# DRIVERS_CONNECTORS.net
KiCad netlist of a schematic drawn in Altium Designer
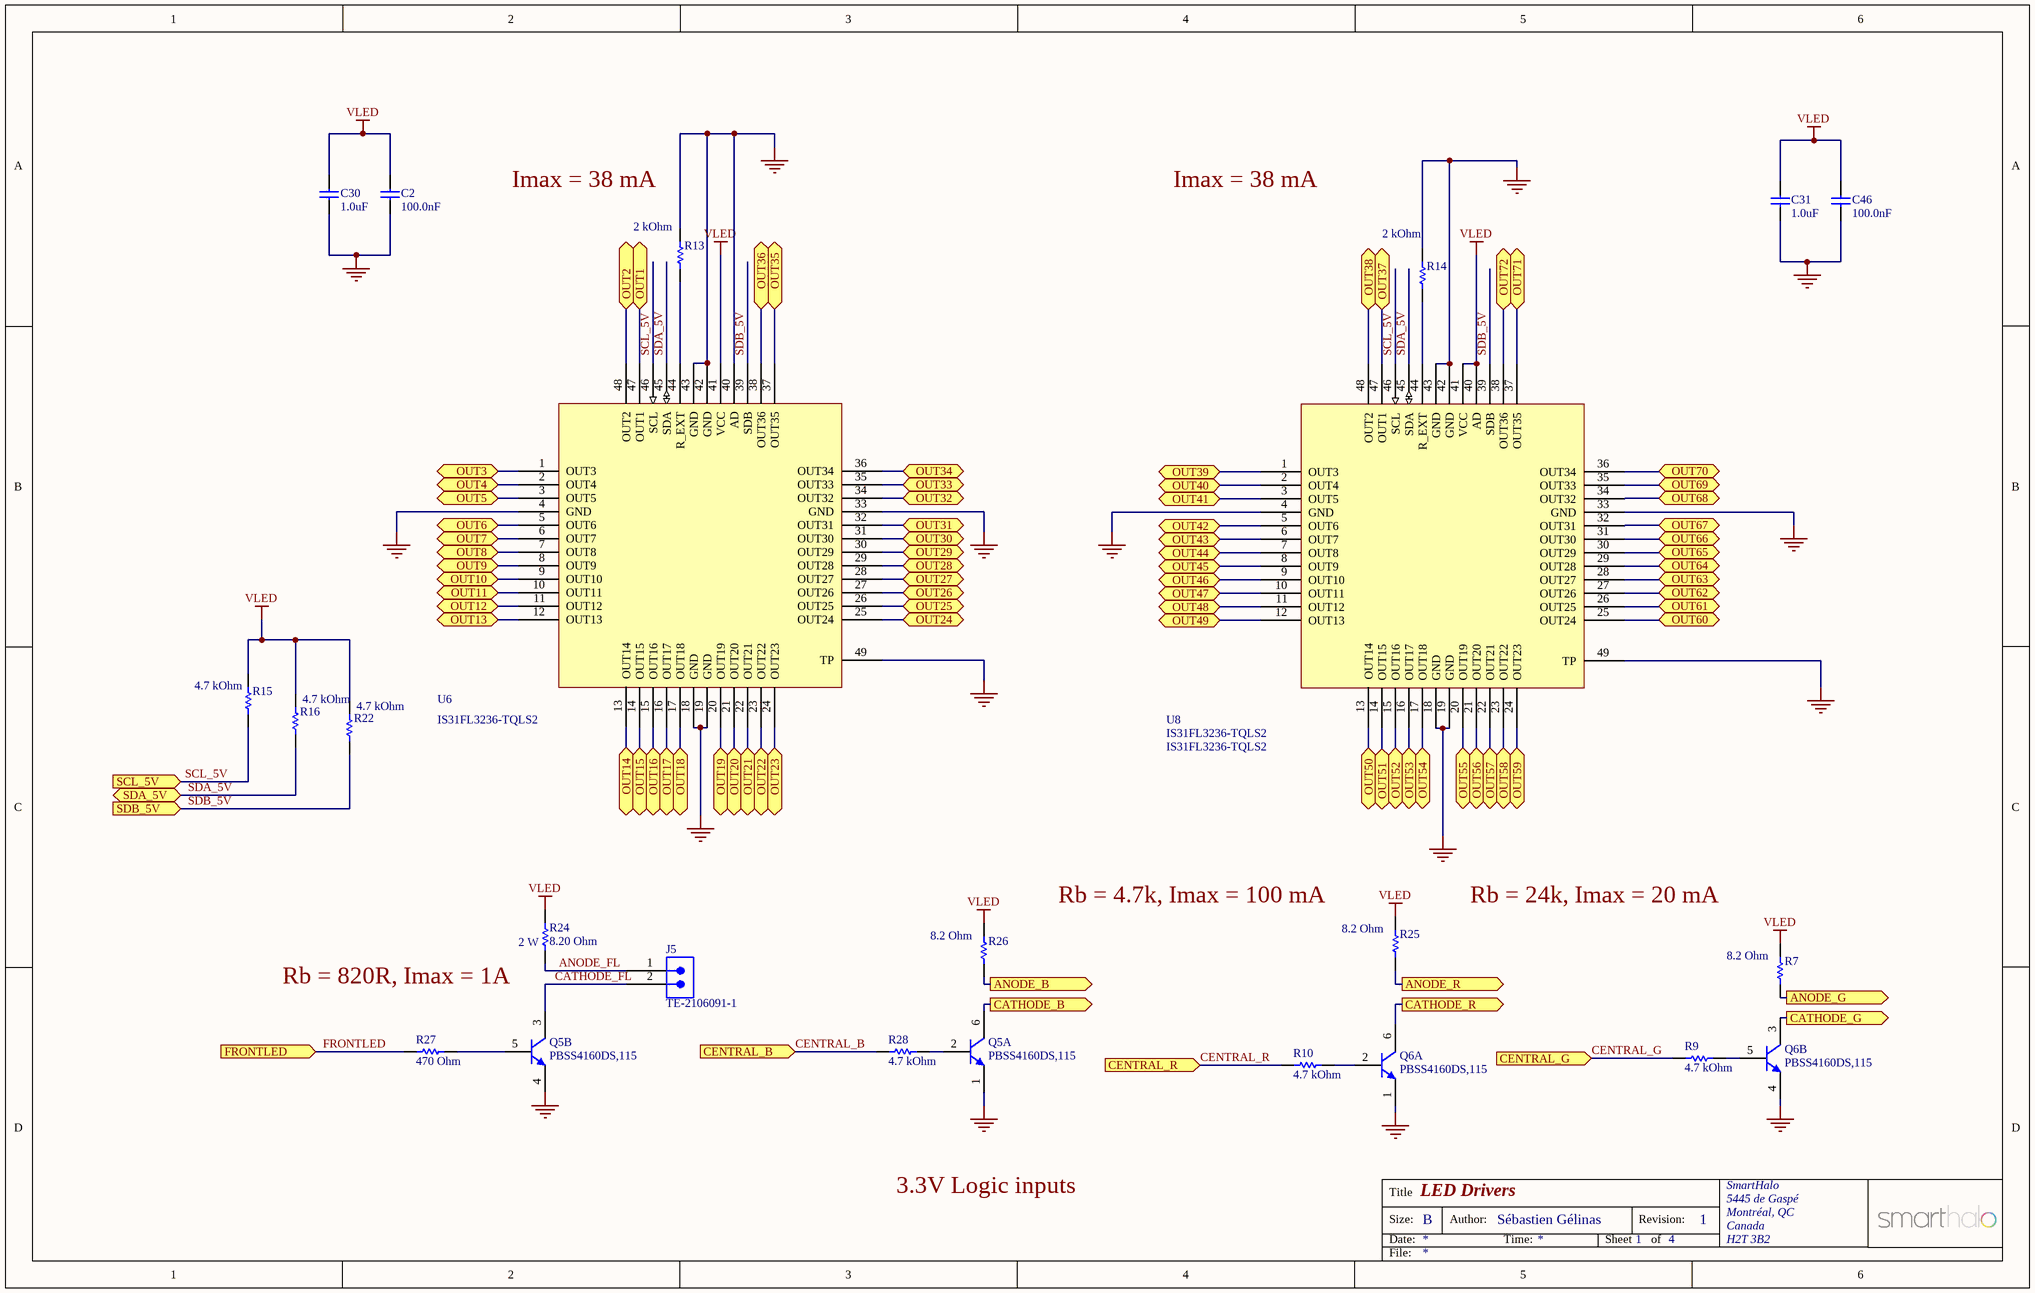
[diagram p0: DRIVERS_CONNECTORS.SchDoc]

(export (version "E")
  (design (tool "Eeschema 10.0.6"))
  (components
    (comp (ref "C2")
      (value "100.0nF")
      (footprint "CAPC0603(1608)100_N")
      (description "Chip Cap 0603 X7R 10%")
      (fields (field (name "PART NUMBER") "C0402-1n0") (field (name "PUBLISHER") "Nordic Semiconductor"))
      (libsource (lib "SmartHalo") (part "CAP0603"))
    )
    (comp (ref "C30")
      (value "1.0uF")
      (footprint "CAPC0603(1608)100_N")
      (description "Chip Cap 0603 X7R 10%")
      (fields (field (name "PART NUMBER") "C0402-1n0") (field (name "PUBLISHER") "Nordic Semiconductor"))
      (libsource (lib "SmartHalo") (part "CAP0603"))
    )
    (comp (ref "C31")
      (value "1.0uF")
      (footprint "CAPC0603(1608)100_N")
      (description "Chip Cap 0603 X7R 10%")
      (fields (field (name "PART NUMBER") "C0402-1n0") (field (name "PUBLISHER") "Nordic Semiconductor"))
      (libsource (lib "SmartHalo") (part "CAP0603"))
    )
    (comp (ref "C46")
      (value "100.0nF")
      (footprint "CAPC0603(1608)100_N")
      (description "Chip Cap 0603 X7R 10%")
      (fields (field (name "PART NUMBER") "C0402-1n0") (field (name "PUBLISHER") "Nordic Semiconductor"))
      (libsource (lib "SmartHalo") (part "CAP0603"))
    )
    (comp (ref "J5")
      (value "TE-2106091-1")
      (footprint "TE-2106091-1")
      (description "2 pos Inverted Thru Board SMT Header")
      (fields (field (name "MANUFACTURER") "TE") (field (name "MANUFACTURER PART NUMBER") "2106091"))
      (libsource (lib "SmartHalo") (part "TE-2106091-1"))
    )
    (comp (ref "Q5")
      (value "PBSS4160DS,115")
      (footprint "SmartHalo:NXP-SC74_M")
      (description "TRANS 2NPN 60V 1A 6TSOP")
      (fields (field (name "PARTNUMBER") "PBSS4160DS") (field (name "MANUFACTURER") "NXP Semiconductors"))
      (libsource (lib "SmartHalo_Symbols") (part "PBSS4160DS,115"))
    )
    (comp (ref "Q6")
      (value "PBSS4160DS,115")
      (footprint "SmartHalo:NXP-SC74_M")
      (description "TRANS 2NPN 60V 1A 6TSOP")
      (fields (field (name "PARTNUMBER") "PBSS4160DS") (field (name "MANUFACTURER") "NXP Semiconductors"))
      (libsource (lib "SmartHalo_Symbols") (part "PBSS4160DS,115"))
    )
    (comp (ref "R7")
      (value "8.2 Ohm")
      (footprint "RESC0603(1608)_N")
      (description "8R2 0.1W 5% 0603 (1608 Metric)  SMD")
      (fields (field (name "TOLERANCE") "5 %") (field (name "POWER") "0.1 W"))
      (libsource (lib "Altium Content Vault") (part "CMP-1012-00090-1"))
    )
    (comp (ref "R9")
      (value "4.7 kOhm")
      (footprint "RESC0603(1608)_N")
      (description "4K7 0.1W 5% 0603 (1608 Metric)  SMD")
      (fields (field (name "TOLERANCE") "5 %") (field (name "POWER") "0.1 W"))
      (libsource (lib "Altium Content Vault") (part "CMP-1012-00090-1"))
    )
    (comp (ref "R10")
      (value "4.7 kOhm")
      (footprint "RESC0603(1608)_N")
      (description "4K7 0.1W 5% 0603 (1608 Metric)  SMD")
      (fields (field (name "TOLERANCE") "5 %") (field (name "POWER") "0.1 W"))
      (libsource (lib "Altium Content Vault") (part "CMP-1012-00090-1"))
    )
    (comp (ref "R13")
      (value "2 kOhm")
      (footprint "RESC0603(1608)_N")
      (description "2k 0.1W 5% 0603 (1608 Metric)  SMD")
      (fields (field (name "TOLERANCE") "5 %") (field (name "POWER") "0.1 W"))
      (libsource (lib "Altium Content Vault") (part "CMP-1012-00090-1"))
    )
    (comp (ref "R14")
      (value "2 kOhm")
      (footprint "RESC0603(1608)_N")
      (description "2k 0.1W 5% 0603 (1608 Metric)  SMD")
      (fields (field (name "TOLERANCE") "5 %") (field (name "POWER") "0.1 W"))
      (libsource (lib "Altium Content Vault") (part "CMP-1012-00090-1"))
    )
    (comp (ref "R15")
      (value "4.7 kOhm")
      (footprint "RESC0603(1608)_N")
      (description "4K7 0.1W 5% 0603 (1608 Metric)  SMD")
      (fields (field (name "TOLERANCE") "5 %") (field (name "POWER") "0.1 W"))
      (libsource (lib "Altium Content Vault") (part "CMP-1012-00090-1"))
    )
    (comp (ref "R16")
      (value "4.7 kOhm")
      (footprint "RESC0603(1608)_N")
      (description "4K7 0.1W 5% 0603 (1608 Metric)  SMD")
      (fields (field (name "TOLERANCE") "5 %") (field (name "POWER") "0.1 W"))
      (libsource (lib "Altium Content Vault") (part "CMP-1012-00090-1"))
    )
    (comp (ref "R22")
      (value "4.7 kOhm")
      (footprint "RESC0603(1608)_N")
      (description "4K7 0.1W 5% 0603 (1608 Metric)  SMD")
      (fields (field (name "TOLERANCE") "5 %") (field (name "POWER") "0.1 W"))
      (libsource (lib "Altium Content Vault") (part "CMP-1012-00090-1"))
    )
    (comp (ref "R24")
      (value "8.20 Ohm")
      (footprint "RESC2512(6432)_L")
      (description "8R2 2W 5% 2512 (6432 Metric)  SMD")
      (fields (field (name "TOLERANCE") "5 %") (field (name "POWER") "2 W"))
      (libsource (lib "Altium Content Vault") (part "CMP-1018-00024-1"))
    )
    (comp (ref "R25")
      (value "8.2 Ohm")
      (footprint "RESC0603(1608)_N")
      (description "8R2 0.1W 5% 0603 (1608 Metric)  SMD")
      (fields (field (name "TOLERANCE") "5 %") (field (name "POWER") "0.1 W"))
      (libsource (lib "Altium Content Vault") (part "CMP-1012-00090-1"))
    )
    (comp (ref "R26")
      (value "8.2 Ohm")
      (footprint "RESC0603(1608)_N")
      (description "8R2 0.1W 5% 0603 (1608 Metric)  SMD")
      (fields (field (name "TOLERANCE") "5 %") (field (name "POWER") "0.1 W"))
      (libsource (lib "Altium Content Vault") (part "CMP-1012-00090-1"))
    )
    (comp (ref "R27")
      (value "470 Ohm")
      (footprint "RESC0603(1608)_N")
      (description "470R 1/16W 5% 0603 (1608 Metric)  SMD")
      (fields (field (name "TOLERANCE") "5 %") (field (name "POWER") "1/16 W"))
      (libsource (lib "Altium Content Vault") (part "CMP-1012-00090-1"))
    )
    (comp (ref "R28")
      (value "4.7 kOhm")
      (footprint "RESC0603(1608)_N")
      (description "4K7 0.1W 5% 0603 (1608 Metric)  SMD")
      (fields (field (name "TOLERANCE") "5 %") (field (name "POWER") "0.1 W"))
      (libsource (lib "Altium Content Vault") (part "CMP-1012-00090-1"))
    )
    (comp (ref "U6")
      (value "IS31FL3236-TQLS2")
      (footprint "TQFP48")
      (description "IC 36 CHANNELS LED DRIVER")
      (fields (field (name "MANUFACTURER") "ISSI"))
      (libsource (lib "SmartHalo") (part "IS31FL3236-TQLS2"))
    )
    (comp (ref "U8")
      (value "IS31FL3236-TQLS2")
      (footprint "TQFP48")
      (description "IC 36 CHANNELS LED DRIVER")
      (fields
        (field (name "MANUFACTURER") "ISSI")
        (field (name "MANUFACTURER PART NUMBER") "IS31FL3236-TQLS2")
      )
      (libsource (lib "SmartHalo") (part "IS31FL3236-TQLS2"))
    )
  )
  (nets
    (net (code "1") (name "/ANODE_B") (class "Default")
      (node (ref "R26") (pin "1") (pinfunction "1_1") (pintype "passive"))
    )
    (net (code "2") (name "/ANODE_FL") (class "Default")
      (node (ref "J5") (pin "1") (pinfunction "1_1") (pintype "passive"))
      (node (ref "R24") (pin "1") (pinfunction "1_1") (pintype "passive"))
    )
    (net (code "3") (name "/ANODE_G") (class "Default")
      (node (ref "R7") (pin "1") (pinfunction "1_1") (pintype "passive"))
    )
    (net (code "4") (name "/ANODE_R") (class "Default")
      (node (ref "R25") (pin "1") (pinfunction "1_1") (pintype "passive"))
    )
    (net (code "5") (name "/CATHODE_B") (class "Default")
      (node (ref "Q5") (pin "6") (pinfunction "C1_6") (pintype "passive"))
    )
    (net (code "6") (name "/CATHODE_FL") (class "Default")
      (node (ref "J5") (pin "2") (pinfunction "2_2") (pintype "passive"))
      (node (ref "Q5") (pin "3") (pinfunction "C2_3") (pintype "passive"))
    )
    (net (code "7") (name "/CATHODE_G") (class "Default")
      (node (ref "Q6") (pin "3") (pinfunction "C2_3") (pintype "passive"))
    )
    (net (code "8") (name "/CATHODE_R") (class "Default")
      (node (ref "Q6") (pin "6") (pinfunction "C1_6") (pintype "passive"))
    )
    (net (code "9") (name "/CENTRAL_B") (class "Default")
      (node (ref "R28") (pin "2") (pinfunction "2_2") (pintype "passive"))
    )
    (net (code "10") (name "/CENTRAL_G") (class "Default")
      (node (ref "R9") (pin "2") (pinfunction "2_2") (pintype "passive"))
    )
    (net (code "11") (name "/CENTRAL_R") (class "Default")
      (node (ref "R10") (pin "2") (pinfunction "2_2") (pintype "passive"))
    )
    (net (code "12") (name "/FRONTLED") (class "Default")
      (node (ref "R27") (pin "2") (pinfunction "2_2") (pintype "passive"))
    )
    (net (code "13") (name "/OUT1") (class "Default")
      (node (ref "U6") (pin "47") (pinfunction "OUT1_47") (pintype "passive"))
    )
    (net (code "14") (name "/OUT2") (class "Default")
      (node (ref "U6") (pin "48") (pinfunction "OUT2_48") (pintype "passive"))
    )
    (net (code "15") (name "/OUT3") (class "Default")
      (node (ref "U6") (pin "1") (pinfunction "OUT3_1") (pintype "passive"))
    )
    (net (code "16") (name "/OUT4") (class "Default")
      (node (ref "U6") (pin "2") (pinfunction "OUT4_2") (pintype "passive"))
    )
    (net (code "17") (name "/OUT5") (class "Default")
      (node (ref "U6") (pin "3") (pinfunction "OUT5_3") (pintype "passive"))
    )
    (net (code "18") (name "/OUT6") (class "Default")
      (node (ref "U6") (pin "5") (pinfunction "OUT6_5") (pintype "passive"))
    )
    (net (code "19") (name "/OUT7") (class "Default")
      (node (ref "U6") (pin "6") (pinfunction "OUT7_6") (pintype "passive"))
    )
    (net (code "20") (name "/OUT8") (class "Default")
      (node (ref "U6") (pin "7") (pinfunction "OUT8_7") (pintype "passive"))
    )
    (net (code "21") (name "/OUT9") (class "Default")
      (node (ref "U6") (pin "8") (pinfunction "OUT9_8") (pintype "passive"))
    )
    (net (code "22") (name "/OUT10") (class "Default")
      (node (ref "U6") (pin "9") (pinfunction "OUT10_9") (pintype "passive"))
    )
    (net (code "23") (name "/OUT11") (class "Default")
      (node (ref "U6") (pin "10") (pinfunction "OUT11_10") (pintype "passive"))
    )
    (net (code "24") (name "/OUT12") (class "Default")
      (node (ref "U6") (pin "11") (pinfunction "OUT12_11") (pintype "passive"))
    )
    (net (code "25") (name "/OUT13") (class "Default")
      (node (ref "U6") (pin "12") (pinfunction "OUT13_12") (pintype "passive"))
    )
    (net (code "26") (name "/OUT14") (class "Default")
      (node (ref "U6") (pin "13") (pinfunction "OUT14_13") (pintype "passive"))
    )
    (net (code "27") (name "/OUT15") (class "Default")
      (node (ref "U6") (pin "14") (pinfunction "OUT15_14") (pintype "passive"))
    )
    (net (code "28") (name "/OUT16") (class "Default")
      (node (ref "U6") (pin "15") (pinfunction "OUT16_15") (pintype "passive"))
    )
    (net (code "29") (name "/OUT17") (class "Default")
      (node (ref "U6") (pin "16") (pinfunction "OUT17_16") (pintype "passive"))
    )
    (net (code "30") (name "/OUT18") (class "Default")
      (node (ref "U6") (pin "17") (pinfunction "OUT18_17") (pintype "passive"))
    )
    (net (code "31") (name "/OUT19") (class "Default")
      (node (ref "U6") (pin "20") (pinfunction "OUT19_20") (pintype "passive"))
    )
    (net (code "32") (name "/OUT20") (class "Default")
      (node (ref "U6") (pin "21") (pinfunction "OUT20_21") (pintype "passive"))
    )
    (net (code "33") (name "/OUT21") (class "Default")
      (node (ref "U6") (pin "22") (pinfunction "OUT21_22") (pintype "passive"))
    )
    (net (code "34") (name "/OUT22") (class "Default")
      (node (ref "U6") (pin "23") (pinfunction "OUT22_23") (pintype "passive"))
    )
    (net (code "35") (name "/OUT23") (class "Default")
      (node (ref "U6") (pin "24") (pinfunction "OUT23_24") (pintype "passive"))
    )
    (net (code "36") (name "/OUT24") (class "Default")
      (node (ref "U6") (pin "25") (pinfunction "OUT24_25") (pintype "passive"))
    )
    (net (code "37") (name "/OUT25") (class "Default")
      (node (ref "U6") (pin "26") (pinfunction "OUT25_26") (pintype "passive"))
    )
    (net (code "38") (name "/OUT26") (class "Default")
      (node (ref "U6") (pin "27") (pinfunction "OUT26_27") (pintype "passive"))
    )
    (net (code "39") (name "/OUT27") (class "Default")
      (node (ref "U6") (pin "28") (pinfunction "OUT27_28") (pintype "passive"))
    )
    (net (code "40") (name "/OUT28") (class "Default")
      (node (ref "U6") (pin "29") (pinfunction "OUT28_29") (pintype "passive"))
    )
    (net (code "41") (name "/OUT29") (class "Default")
      (node (ref "U6") (pin "30") (pinfunction "OUT29_30") (pintype "passive"))
    )
    (net (code "42") (name "/OUT30") (class "Default")
      (node (ref "U6") (pin "31") (pinfunction "OUT30_31") (pintype "passive"))
    )
    (net (code "43") (name "/OUT31") (class "Default")
      (node (ref "U6") (pin "32") (pinfunction "OUT31_32") (pintype "passive"))
    )
    (net (code "44") (name "/OUT32") (class "Default")
      (node (ref "U6") (pin "34") (pinfunction "OUT32_34") (pintype "passive"))
    )
    (net (code "45") (name "/OUT33") (class "Default")
      (node (ref "U6") (pin "35") (pinfunction "OUT33_35") (pintype "passive"))
    )
    (net (code "46") (name "/OUT34") (class "Default")
      (node (ref "U6") (pin "36") (pinfunction "OUT34_36") (pintype "passive"))
    )
    (net (code "47") (name "/OUT35") (class "Default")
      (node (ref "U6") (pin "37") (pinfunction "OUT35_37") (pintype "passive"))
    )
    (net (code "48") (name "/OUT36") (class "Default")
      (node (ref "U6") (pin "38") (pinfunction "OUT36_38") (pintype "passive"))
    )
    (net (code "49") (name "/OUT37") (class "Default")
      (node (ref "U8") (pin "47") (pinfunction "OUT1_47") (pintype "passive"))
    )
    (net (code "50") (name "/OUT38") (class "Default")
      (node (ref "U8") (pin "48") (pinfunction "OUT2_48") (pintype "passive"))
    )
    (net (code "51") (name "/OUT39") (class "Default")
      (node (ref "U8") (pin "1") (pinfunction "OUT3_1") (pintype "passive"))
    )
    (net (code "52") (name "/OUT40") (class "Default")
      (node (ref "U8") (pin "2") (pinfunction "OUT4_2") (pintype "passive"))
    )
    (net (code "53") (name "/OUT41") (class "Default")
      (node (ref "U8") (pin "3") (pinfunction "OUT5_3") (pintype "passive"))
    )
    (net (code "54") (name "/OUT42") (class "Default")
      (node (ref "U8") (pin "5") (pinfunction "OUT6_5") (pintype "passive"))
    )
    (net (code "55") (name "/OUT43") (class "Default")
      (node (ref "U8") (pin "6") (pinfunction "OUT7_6") (pintype "passive"))
    )
    (net (code "56") (name "/OUT44") (class "Default")
      (node (ref "U8") (pin "7") (pinfunction "OUT8_7") (pintype "passive"))
    )
    (net (code "57") (name "/OUT45") (class "Default")
      (node (ref "U8") (pin "8") (pinfunction "OUT9_8") (pintype "passive"))
    )
    (net (code "58") (name "/OUT46") (class "Default")
      (node (ref "U8") (pin "9") (pinfunction "OUT10_9") (pintype "passive"))
    )
    (net (code "59") (name "/OUT47") (class "Default")
      (node (ref "U8") (pin "10") (pinfunction "OUT11_10") (pintype "passive"))
    )
    (net (code "60") (name "/OUT48") (class "Default")
      (node (ref "U8") (pin "11") (pinfunction "OUT12_11") (pintype "passive"))
    )
    (net (code "61") (name "/OUT49") (class "Default")
      (node (ref "U8") (pin "12") (pinfunction "OUT13_12") (pintype "passive"))
    )
    (net (code "62") (name "/OUT50") (class "Default")
      (node (ref "U8") (pin "13") (pinfunction "OUT14_13") (pintype "passive"))
    )
    (net (code "63") (name "/OUT51") (class "Default")
      (node (ref "U8") (pin "14") (pinfunction "OUT15_14") (pintype "passive"))
    )
    (net (code "64") (name "/OUT52") (class "Default")
      (node (ref "U8") (pin "15") (pinfunction "OUT16_15") (pintype "passive"))
    )
    (net (code "65") (name "/OUT53") (class "Default")
      (node (ref "U8") (pin "16") (pinfunction "OUT17_16") (pintype "passive"))
    )
    (net (code "66") (name "/OUT54") (class "Default")
      (node (ref "U8") (pin "17") (pinfunction "OUT18_17") (pintype "passive"))
    )
    (net (code "67") (name "/OUT55") (class "Default")
      (node (ref "U8") (pin "20") (pinfunction "OUT19_20") (pintype "passive"))
    )
    (net (code "68") (name "/OUT56") (class "Default")
      (node (ref "U8") (pin "21") (pinfunction "OUT20_21") (pintype "passive"))
    )
    (net (code "69") (name "/OUT57") (class "Default")
      (node (ref "U8") (pin "22") (pinfunction "OUT21_22") (pintype "passive"))
    )
    (net (code "70") (name "/OUT58") (class "Default")
      (node (ref "U8") (pin "23") (pinfunction "OUT22_23") (pintype "passive"))
    )
    (net (code "71") (name "/OUT59") (class "Default")
      (node (ref "U8") (pin "24") (pinfunction "OUT23_24") (pintype "passive"))
    )
    (net (code "72") (name "/OUT60") (class "Default")
      (node (ref "U8") (pin "25") (pinfunction "OUT24_25") (pintype "passive"))
    )
    (net (code "73") (name "/OUT61") (class "Default")
      (node (ref "U8") (pin "26") (pinfunction "OUT25_26") (pintype "passive"))
    )
    (net (code "74") (name "/OUT62") (class "Default")
      (node (ref "U8") (pin "27") (pinfunction "OUT26_27") (pintype "passive"))
    )
    (net (code "75") (name "/OUT63") (class "Default")
      (node (ref "U8") (pin "28") (pinfunction "OUT27_28") (pintype "passive"))
    )
    (net (code "76") (name "/OUT64") (class "Default")
      (node (ref "U8") (pin "29") (pinfunction "OUT28_29") (pintype "passive"))
    )
    (net (code "77") (name "/OUT65") (class "Default")
      (node (ref "U8") (pin "30") (pinfunction "OUT29_30") (pintype "passive"))
    )
    (net (code "78") (name "/OUT66") (class "Default")
      (node (ref "U8") (pin "31") (pinfunction "OUT30_31") (pintype "passive"))
    )
    (net (code "79") (name "/OUT67") (class "Default")
      (node (ref "U8") (pin "32") (pinfunction "OUT31_32") (pintype "passive"))
    )
    (net (code "80") (name "/OUT68") (class "Default")
      (node (ref "U8") (pin "34") (pinfunction "OUT32_34") (pintype "passive"))
    )
    (net (code "81") (name "/OUT69") (class "Default")
      (node (ref "U8") (pin "35") (pinfunction "OUT33_35") (pintype "passive"))
    )
    (net (code "82") (name "/OUT70") (class "Default")
      (node (ref "U8") (pin "36") (pinfunction "OUT34_36") (pintype "passive"))
    )
    (net (code "83") (name "/OUT71") (class "Default")
      (node (ref "U8") (pin "37") (pinfunction "OUT35_37") (pintype "passive"))
    )
    (net (code "84") (name "/OUT72") (class "Default")
      (node (ref "U8") (pin "38") (pinfunction "OUT36_38") (pintype "passive"))
    )
    (net (code "85") (name "/SCL_5V") (class "Default")
      (node (ref "R15") (pin "1") (pinfunction "1_1") (pintype "passive"))
      (node (ref "U6") (pin "46") (pinfunction "SCL_46") (pintype "input"))
      (node (ref "U8") (pin "46") (pinfunction "SCL_46") (pintype "input"))
    )
    (net (code "86") (name "/SDA_5V") (class "Default")
      (node (ref "R16") (pin "1") (pinfunction "1_1") (pintype "passive"))
      (node (ref "U6") (pin "45") (pinfunction "SDA_45") (pintype "bidirectional"))
      (node (ref "U8") (pin "45") (pinfunction "SDA_45") (pintype "bidirectional"))
    )
    (net (code "87") (name "/SDB_5V") (class "Default")
      (node (ref "R22") (pin "1") (pinfunction "1_1") (pintype "passive"))
      (node (ref "U6") (pin "39") (pinfunction "SDB_39") (pintype "passive"))
      (node (ref "U8") (pin "39") (pinfunction "SDB_39") (pintype "passive"))
    )
    (net (code "88") (name "GND") (class "Default")
      (node (ref "C2") (pin "2") (pinfunction "2_2") (pintype "passive"))
      (node (ref "C30") (pin "2") (pinfunction "2_2") (pintype "passive"))
      (node (ref "C31") (pin "2") (pinfunction "2_2") (pintype "passive"))
      (node (ref "C46") (pin "2") (pinfunction "2_2") (pintype "passive"))
      (node (ref "Q5") (pin "1") (pinfunction "E1_1") (pintype "passive"))
      (node (ref "Q5") (pin "4") (pinfunction "E2_4") (pintype "passive"))
      (node (ref "Q6") (pin "1") (pinfunction "E1_1") (pintype "passive"))
      (node (ref "Q6") (pin "4") (pinfunction "E2_4") (pintype "passive"))
      (node (ref "R13") (pin "2") (pinfunction "2_2") (pintype "passive"))
      (node (ref "R14") (pin "2") (pinfunction "2_2") (pintype "passive"))
      (node (ref "U6") (pin "18") (pinfunction "GND_18") (pintype "power_in"))
      (node (ref "U6") (pin "19") (pinfunction "GND_19") (pintype "power_in"))
      (node (ref "U6") (pin "33") (pinfunction "GND_33") (pintype "power_in"))
      (node (ref "U6") (pin "4") (pinfunction "GND_4") (pintype "power_in"))
      (node (ref "U6") (pin "40") (pinfunction "AD_40") (pintype "passive"))
      (node (ref "U6") (pin "42") (pinfunction "GND_42") (pintype "power_in"))
      (node (ref "U6") (pin "43") (pinfunction "GND_43") (pintype "power_in"))
      (node (ref "U6") (pin "49") (pinfunction "TP_49") (pintype "power_in"))
      (node (ref "U8") (pin "18") (pinfunction "GND_18") (pintype "power_in"))
      (node (ref "U8") (pin "19") (pinfunction "GND_19") (pintype "power_in"))
      (node (ref "U8") (pin "33") (pinfunction "GND_33") (pintype "power_in"))
      (node (ref "U8") (pin "4") (pinfunction "GND_4") (pintype "power_in"))
      (node (ref "U8") (pin "42") (pinfunction "GND_42") (pintype "power_in"))
      (node (ref "U8") (pin "43") (pinfunction "GND_43") (pintype "power_in"))
      (node (ref "U8") (pin "49") (pinfunction "TP_49") (pintype "power_in"))
    )
    (net (code "89") (name "Net-(Q5A-B1)") (class "Default")
      (node (ref "Q5") (pin "2") (pinfunction "B1_2") (pintype "passive"))
      (node (ref "R28") (pin "1") (pinfunction "1_1") (pintype "passive"))
    )
    (net (code "90") (name "Net-(Q5B-B2)") (class "Default")
      (node (ref "Q5") (pin "5") (pinfunction "B2_5") (pintype "passive"))
      (node (ref "R27") (pin "1") (pinfunction "1_1") (pintype "passive"))
    )
    (net (code "91") (name "Net-(Q6A-B1)") (class "Default")
      (node (ref "Q6") (pin "2") (pinfunction "B1_2") (pintype "passive"))
      (node (ref "R10") (pin "1") (pinfunction "1_1") (pintype "passive"))
    )
    (net (code "92") (name "Net-(Q6B-B2)") (class "Default")
      (node (ref "Q6") (pin "5") (pinfunction "B2_5") (pintype "passive"))
      (node (ref "R9") (pin "1") (pinfunction "1_1") (pintype "passive"))
    )
    (net (code "93") (name "Net-(U6-R_EXT)") (class "Default")
      (node (ref "R13") (pin "1") (pinfunction "1_1") (pintype "passive"))
      (node (ref "U6") (pin "44") (pinfunction "R_EXT_44") (pintype "passive"))
    )
    (net (code "94") (name "Net-(U8-R_EXT)") (class "Default")
      (node (ref "R14") (pin "1") (pinfunction "1_1") (pintype "passive"))
      (node (ref "U8") (pin "44") (pinfunction "R_EXT_44") (pintype "passive"))
    )
    (net (code "95") (name "VLED") (class "Default")
      (node (ref "C2") (pin "1") (pinfunction "1_1") (pintype "passive"))
      (node (ref "C30") (pin "1") (pinfunction "1_1") (pintype "passive"))
      (node (ref "C31") (pin "1") (pinfunction "1_1") (pintype "passive"))
      (node (ref "C46") (pin "1") (pinfunction "1_1") (pintype "passive"))
      (node (ref "R15") (pin "2") (pinfunction "2_2") (pintype "passive"))
      (node (ref "R16") (pin "2") (pinfunction "2_2") (pintype "passive"))
      (node (ref "R22") (pin "2") (pinfunction "2_2") (pintype "passive"))
      (node (ref "R24") (pin "2") (pinfunction "2_2") (pintype "passive"))
      (node (ref "R25") (pin "2") (pinfunction "2_2") (pintype "passive"))
      (node (ref "R26") (pin "2") (pinfunction "2_2") (pintype "passive"))
      (node (ref "R7") (pin "2") (pinfunction "2_2") (pintype "passive"))
      (node (ref "U6") (pin "41") (pinfunction "VCC_41") (pintype "power_in"))
      (node (ref "U8") (pin "40") (pinfunction "AD_40") (pintype "passive"))
      (node (ref "U8") (pin "41") (pinfunction "VCC_41") (pintype "power_in"))
    )
  )
)
